# mcu_battery.net
KiCad netlist of a schematic drawn in EAGLE
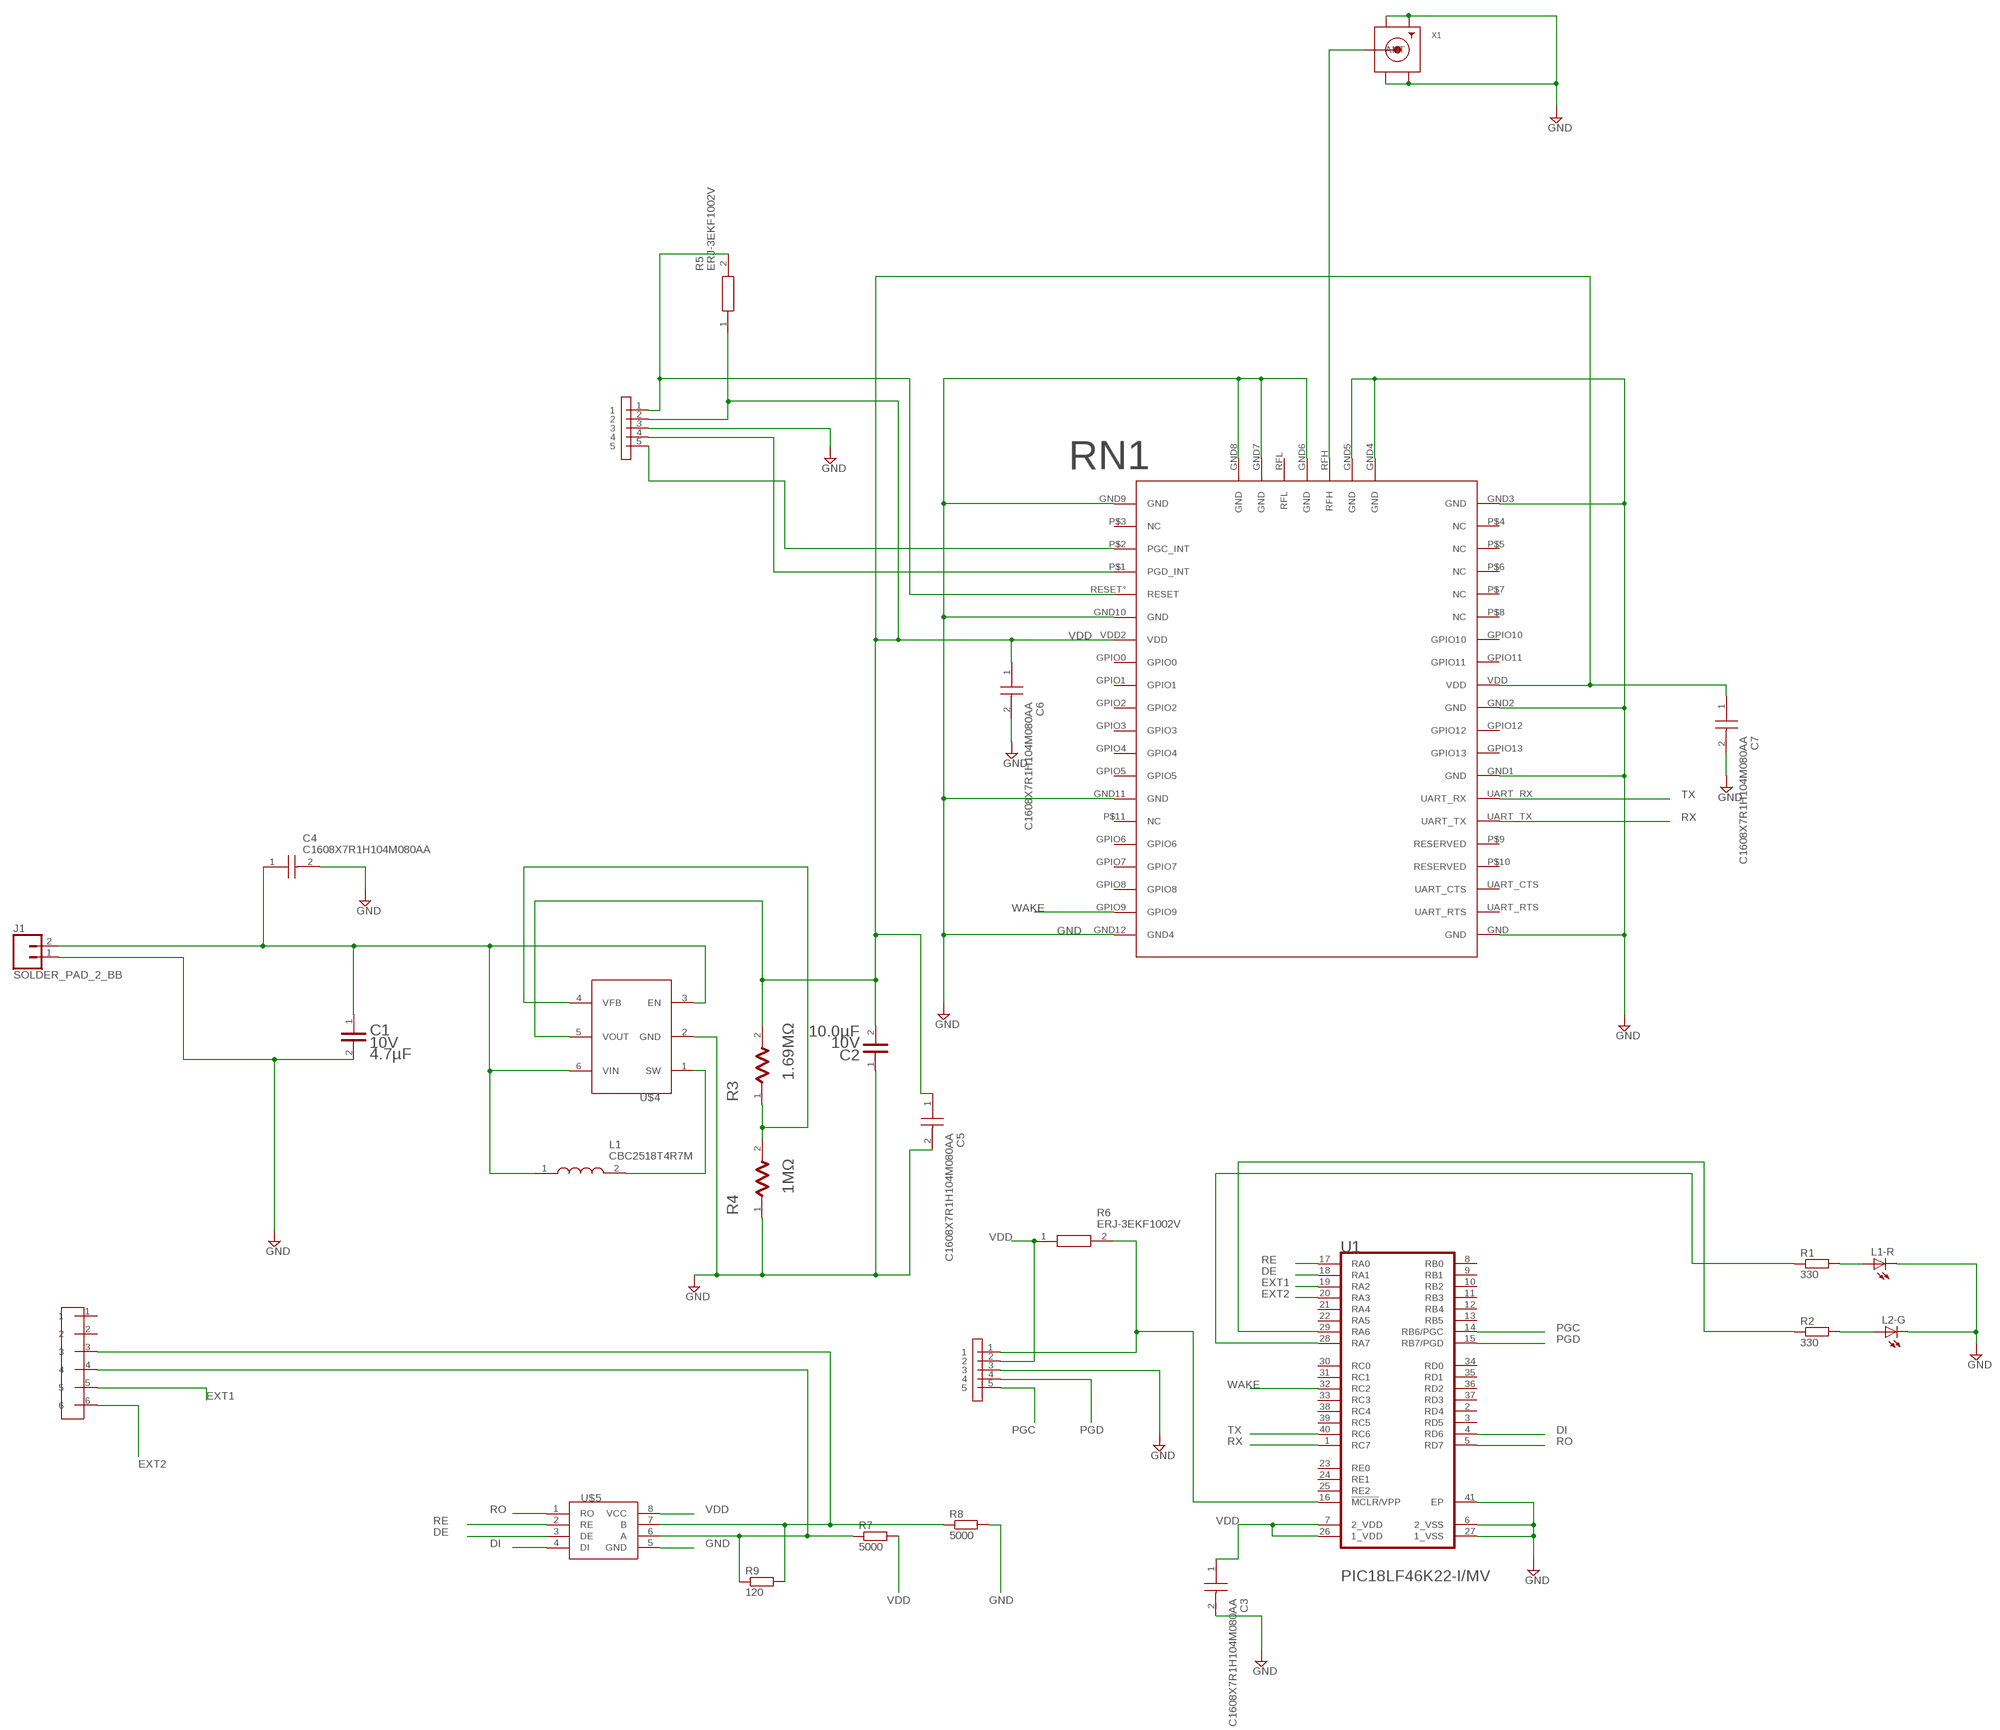
[diagram p0: schematic, sheet 1]

(export (version "E")
  (design (tool "Eeschema 10.0.6"))
  (components
    (comp (ref "C1")
      (value "KEMET_C0603C475K8PACTUKEMET_C0603C475K8PACTU_0_0")
      (footprint "eagle-import:KEMET_C0603C475K8PACTU_0")
      (fields
        (field (name "DIGIKEY_PART_NUMBER") "399-5503-1-ND")
        (field (name "MF") "Kemet")
        (field (name "MOUSER_PART_NUMBER") "80-C0603C475K8P")
      )
      (libsource (lib "eagle-import") (part "KEMET_C0603C475K8PACTUKEMET_C0603C475K8PACTU_0_0"))
    )
    (comp (ref "C2")
      (value "TDK_C1608X5R1A106M080ACTDK_C1608X5R1A106M080AC_0_0")
      (footprint "eagle-import:TDK_C1608X5R1A106M080AC_0")
      (fields
        (field (name "DIGIKEY_PART_NUMBER") "445-6853-1-ND")
        (field (name "MF") "TDK")
        (field (name "MOUSER_PART_NUMBER") "810-C1608X5R1A106M")
      )
      (libsource (lib "eagle-import") (part "TDK_C1608X5R1A106M080ACTDK_C1608X5R1A106M080AC_0_0"))
    )
    (comp (ref "C3")
      (value "C1608X7R1H104M080AA")
      (footprint "eagle-import:CAPC1608X80N")
      (fields (field (name "MOUSER_PART_NUMBER") "810-C1608X7R1H104M"))
      (libsource (lib "eagle-import") (part "C1608X7R1H104M080AA"))
    )
    (comp (ref "C4")
      (value "C1608X7R1H104M080AA")
      (footprint "eagle-import:CAPC1608X80N")
      (fields (field (name "MOUSER_PART_NUMBER") "810-C1608X7R1H104M"))
      (libsource (lib "eagle-import") (part "C1608X7R1H104M080AA"))
    )
    (comp (ref "C5")
      (value "C1608X7R1H104M080AA")
      (footprint "eagle-import:CAPC1608X80N")
      (fields (field (name "MOUSER_PART_NUMBER") "810-C1608X7R1H104M"))
      (libsource (lib "eagle-import") (part "C1608X7R1H104M080AA"))
    )
    (comp (ref "C6")
      (value "C1608X7R1H104M080AA")
      (footprint "eagle-import:CAPC1608X80N")
      (fields (field (name "MOUSER_PART_NUMBER") "810-C1608X7R1H104M"))
      (libsource (lib "eagle-import") (part "C1608X7R1H104M080AA"))
    )
    (comp (ref "C7")
      (value "C1608X7R1H104M080AA")
      (footprint "eagle-import:CAPC1608X80N")
      (fields (field (name "MOUSER_PART_NUMBER") "810-C1608X7R1H104M"))
      (libsource (lib "eagle-import") (part "C1608X7R1H104M080AA"))
    )
    (comp (ref "J1")
      (value "SOLDER_PAD_2_BB")
      (footprint "eagle-import:SOLDER_PAD_2")
      (libsource (lib "eagle-import") (part "SOLDER_PAD_2_BB"))
    )
    (comp (ref "L1")
      (value "CBC2518T4R7M")
      (footprint "eagle-import:INDC2518X200N")
      (fields (field (name "MOUSER_PART_NUMBER") "963-CBC2518T4R7M"))
      (libsource (lib "eagle-import") (part "CBC2518T4R7M"))
    )
    (comp (ref "L1-R")
      (value "LEDCHIP-LED0603")
      (footprint "eagle-import:CHIP-LED0603")
      (libsource (lib "eagle-import") (part "LEDCHIP-LED0603"))
    )
    (comp (ref "L2-G")
      (value "LEDCHIP-LED0603")
      (footprint "eagle-import:CHIP-LED0603")
      (libsource (lib "eagle-import") (part "LEDCHIP-LED0603"))
    )
    (comp (ref "R1")
      (value "330")
      (footprint "eagle-import:R0603")
      (libsource (lib "eagle-import") (part "R-EU_R0603"))
    )
    (comp (ref "R2")
      (value "330")
      (footprint "eagle-import:R0603")
      (libsource (lib "eagle-import") (part "R-EU_R0603"))
    )
    (comp (ref "R3")
      (value "VISHAY_CRCW06031M69FKEAVISHAY_CRCW06031M69FKEA_0_1")
      (footprint "eagle-import:VISHAY_CRCW06031M69FKEA_1")
      (fields
        (field (name "APPROVED_ALTERNATE_PART_NUMBER") "541-1.00HHCT-ND")
        (field (name "DIGIKEY_PART_NUMBER") "541-1.69MHTR-ND")
        (field (name "MF") "Vishay")
      )
      (libsource (lib "eagle-import") (part "VISHAY_CRCW06031M69FKEAVISHAY_CRCW06031M69FKEA_0_1"))
    )
    (comp (ref "R4")
      (value "STACKPOLE_RMCF0603FT1M00STACKPOLE_RMCF0603FT1M00_0_1")
      (footprint "eagle-import:STACKPOLE_RMCF0603FT1M00_1")
      (fields
        (field (name "APPROVED_ALTERNATE_PART_NUMBER") "541-1.00HHCT-ND")
        (field (name "DIGIKEY_PART_NUMBER") "RMCF0603FT1M00-ND")
        (field (name "MF") "Stackpole")
      )
      (libsource (lib "eagle-import") (part "STACKPOLE_RMCF0603FT1M00STACKPOLE_RMCF0603FT1M00_0_1"))
    )
    (comp (ref "R5")
      (value "ERJ-3EKF1002V")
      (footprint "eagle-import:RESC1608X55N")
      (fields (field (name "MOUSER_PART_NUMBER") "667-ERJ-3EKF1002V"))
      (libsource (lib "eagle-import") (part "ERJ-3EKF1002V"))
    )
    (comp (ref "R6")
      (value "ERJ-3EKF1002V")
      (footprint "eagle-import:RESC1608X55N")
      (fields (field (name "MOUSER_PART_NUMBER") "667-ERJ-3EKF1002V"))
      (libsource (lib "eagle-import") (part "ERJ-3EKF1002V"))
    )
    (comp (ref "R7")
      (value "5000")
      (footprint "eagle-import:R0805")
      (libsource (lib "eagle-import") (part "R-EU_R0805"))
    )
    (comp (ref "R8")
      (value "5000")
      (footprint "eagle-import:R0805")
      (libsource (lib "eagle-import") (part "R-EU_R0805"))
    )
    (comp (ref "R9")
      (value "120")
      (footprint "eagle-import:R0805")
      (libsource (lib "eagle-import") (part "R-EU_R0805"))
    )
    (comp (ref "RN1")
      (value "NEW_RN2483")
      (footprint "eagle-import:NEW_RN2483")
      (libsource (lib "eagle-import") (part "NEW_RN2483"))
    )
    (comp (ref "U$2")
      (value "ICSP52")
      (footprint "eagle-import:ICSP")
      (libsource (lib "eagle-import") (part "ICSP52"))
    )
    (comp (ref "U$3")
      (value "ICSP_V2")
      (footprint "eagle-import:ICSP_V2")
      (libsource (lib "eagle-import") (part "ICSP_V2"))
    )
    (comp (ref "U$4")
      (value "MCP16252")
      (footprint "eagle-import:MCP16252")
      (libsource (lib "eagle-import") (part "MCP16252"))
    )
    (comp (ref "U$5")
      (value "AMD3485E")
      (footprint "eagle-import:AMD3485E")
      (libsource (lib "eagle-import") (part "AMD3485E"))
    )
    (comp (ref "U1")
      (value "MICROCHIP_PIC18LF46K22-I-MVMICROCHIP_PIC18LF46K22-I-MV_0_1")
      (footprint "eagle-import:MICROCHIP_PIC18LF46K22-I-MV_1")
      (fields (field (name "MF") "Microchip") (field (name "MPN") "PIC18LF46K22-I/MV"))
      (libsource (lib "eagle-import") (part "MICROCHIP_PIC18LF46K22-I-MVMICROCHIP_PIC18LF46K22-I-MV_0_1"))
    )
    (comp (ref "U5")
      (value "CONNECTOR6_V2")
      (footprint "eagle-import:CONNECTOR6_V2")
      (libsource (lib "eagle-import") (part "CONNECTOR6_V2"))
    )
    (comp (ref "X1")
      (value "SMACONNECTOR_EDGE")
      (footprint "eagle-import:SMA_EDGELAUNCH")
      (libsource (lib "eagle-import") (part "SMACONNECTOR_EDGE"))
    )
  )
  (nets
    (net (code "1") (name "/DE") (class "Default")
      (node (ref "U$5") (pin "3") (pinfunction "DE_3") (pintype "bidirectional"))
      (node (ref "U1") (pin "18") (pinfunction "RA1_18") (pintype "bidirectional"))
    )
    (net (code "2") (name "/DI") (class "Default")
      (node (ref "U$5") (pin "4") (pinfunction "DI_4") (pintype "bidirectional"))
      (node (ref "U1") (pin "4") (pinfunction "RD6_4") (pintype "bidirectional"))
    )
    (net (code "3") (name "/EXT1") (class "Default")
      (node (ref "U1") (pin "19") (pinfunction "RA2_19") (pintype "bidirectional"))
      (node (ref "U5") (pin "5") (pinfunction "5_5") (pintype "bidirectional"))
    )
    (net (code "4") (name "/EXT2") (class "Default")
      (node (ref "U1") (pin "20") (pinfunction "RA3_20") (pintype "bidirectional"))
      (node (ref "U5") (pin "6") (pinfunction "6_6") (pintype "bidirectional"))
    )
    (net (code "5") (name "/PGC") (class "Default")
      (node (ref "U$2") (pin "5") (pinfunction "5_5") (pintype "bidirectional"))
      (node (ref "U1") (pin "14") (pinfunction "RB6/PGC_14") (pintype "bidirectional"))
    )
    (net (code "6") (name "/PGD") (class "Default")
      (node (ref "U$2") (pin "4") (pinfunction "4_4") (pintype "bidirectional"))
      (node (ref "U1") (pin "15") (pinfunction "RB7/PGD_15") (pintype "bidirectional"))
    )
    (net (code "7") (name "/RE") (class "Default")
      (node (ref "U$5") (pin "2") (pinfunction "RE_2") (pintype "bidirectional"))
      (node (ref "U1") (pin "17") (pinfunction "RA0_17") (pintype "bidirectional"))
    )
    (net (code "8") (name "/RO") (class "Default")
      (node (ref "U$5") (pin "1") (pinfunction "RO_1") (pintype "bidirectional"))
      (node (ref "U1") (pin "5") (pinfunction "RD7_5") (pintype "bidirectional"))
    )
    (net (code "9") (name "/RX") (class "Default")
      (node (ref "RN1") (pin "UART_TX") (pinfunction "UART_TX_UART_TX") (pintype "bidirectional"))
      (node (ref "U1") (pin "1") (pinfunction "RC7_1") (pintype "bidirectional"))
    )
    (net (code "10") (name "/TX") (class "Default")
      (node (ref "RN1") (pin "UART_RX") (pinfunction "UART_RX_UART_RX") (pintype "bidirectional"))
      (node (ref "U1") (pin "40") (pinfunction "RC6_40") (pintype "bidirectional"))
    )
    (net (code "11") (name "/VDD") (class "Default")
      (node (ref "C2") (pin "2") (pinfunction "2_2") (pintype "bidirectional"))
      (node (ref "C3") (pin "1") (pinfunction "1_1") (pintype "bidirectional"))
      (node (ref "C5") (pin "1") (pinfunction "1_1") (pintype "bidirectional"))
      (node (ref "C6") (pin "1") (pinfunction "1_1") (pintype "bidirectional"))
      (node (ref "C7") (pin "1") (pinfunction "1_1") (pintype "bidirectional"))
      (node (ref "R3") (pin "2") (pinfunction "2_2") (pintype "passive"))
      (node (ref "R5") (pin "1") (pinfunction "1_1") (pintype "bidirectional"))
      (node (ref "R6") (pin "1") (pinfunction "1_1") (pintype "bidirectional"))
      (node (ref "R7") (pin "2") (pinfunction "2_2") (pintype "passive"))
      (node (ref "RN1") (pin "VDD") (pinfunction "VDD_VDD") (pintype "bidirectional"))
      (node (ref "RN1") (pin "VDD2") (pinfunction "VDD_VDD2") (pintype "bidirectional"))
      (node (ref "U$2") (pin "2") (pinfunction "2_2") (pintype "bidirectional"))
      (node (ref "U$3") (pin "2") (pinfunction "2_2") (pintype "bidirectional"))
      (node (ref "U$4") (pin "5") (pinfunction "VOUT_5") (pintype "bidirectional"))
      (node (ref "U$5") (pin "8") (pinfunction "VCC_8") (pintype "bidirectional"))
      (node (ref "U1") (pin "26") (pinfunction "1_VDD_26") (pintype "power_in"))
      (node (ref "U1") (pin "7") (pinfunction "2_VDD_7") (pintype "power_in"))
    )
    (net (code "12") (name "/WAKE") (class "Default")
      (node (ref "RN1") (pin "GPIO9") (pinfunction "GPIO9_GPIO9") (pintype "bidirectional"))
      (node (ref "U1") (pin "32") (pinfunction "RC2_32") (pintype "bidirectional"))
    )
    (net (code "13") (name "GND") (class "Default")
      (node (ref "C1") (pin "2") (pinfunction "2_2") (pintype "bidirectional"))
      (node (ref "C2") (pin "1") (pinfunction "1_1") (pintype "bidirectional"))
      (node (ref "C3") (pin "2") (pinfunction "2_2") (pintype "bidirectional"))
      (node (ref "C4") (pin "2") (pinfunction "2_2") (pintype "bidirectional"))
      (node (ref "C5") (pin "2") (pinfunction "2_2") (pintype "bidirectional"))
      (node (ref "C6") (pin "2") (pinfunction "2_2") (pintype "bidirectional"))
      (node (ref "C7") (pin "2") (pinfunction "2_2") (pintype "bidirectional"))
      (node (ref "J1") (pin "1") (pinfunction "1_1") (pintype "passive"))
      (node (ref "L1-R") (pin "C") (pinfunction "C_C") (pintype "passive"))
      (node (ref "L2-G") (pin "C") (pinfunction "C_C") (pintype "passive"))
      (node (ref "R4") (pin "1") (pinfunction "1_1") (pintype "passive"))
      (node (ref "R8") (pin "2") (pinfunction "2_2") (pintype "passive"))
      (node (ref "RN1") (pin "GND") (pinfunction "GND_GND") (pintype "bidirectional"))
      (node (ref "RN1") (pin "GND1") (pinfunction "GND_GND1") (pintype "bidirectional"))
      (node (ref "RN1") (pin "GND10") (pinfunction "GND_GND10") (pintype "bidirectional"))
      (node (ref "RN1") (pin "GND11") (pinfunction "GND_GND11") (pintype "bidirectional"))
      (node (ref "RN1") (pin "GND12") (pinfunction "GND4_GND12") (pintype "bidirectional"))
      (node (ref "RN1") (pin "GND2") (pinfunction "GND_GND2") (pintype "bidirectional"))
      (node (ref "RN1") (pin "GND3") (pinfunction "GND_GND3") (pintype "bidirectional"))
      (node (ref "RN1") (pin "GND4") (pinfunction "GND_GND4") (pintype "bidirectional"))
      (node (ref "RN1") (pin "GND5") (pinfunction "GND_GND5") (pintype "bidirectional"))
      (node (ref "RN1") (pin "GND6") (pinfunction "GND_GND6") (pintype "bidirectional"))
      (node (ref "RN1") (pin "GND7") (pinfunction "GND_GND7") (pintype "bidirectional"))
      (node (ref "RN1") (pin "GND8") (pinfunction "GND_GND8") (pintype "bidirectional"))
      (node (ref "RN1") (pin "GND9") (pinfunction "GND_GND9") (pintype "bidirectional"))
      (node (ref "U$2") (pin "3") (pinfunction "3_3") (pintype "bidirectional"))
      (node (ref "U$3") (pin "3") (pinfunction "3_3") (pintype "bidirectional"))
      (node (ref "U$4") (pin "2") (pinfunction "GND_2") (pintype "bidirectional"))
      (node (ref "U$5") (pin "5") (pinfunction "GND_5") (pintype "bidirectional"))
      (node (ref "U1") (pin "27") (pinfunction "1_VSS_27") (pintype "power_in"))
      (node (ref "U1") (pin "41") (pinfunction "EP_41") (pintype "passive"))
      (node (ref "U1") (pin "6") (pinfunction "2_VSS_6") (pintype "power_in"))
      (node (ref "X1") (pin "GND@1") (pinfunction "GND4_GND@1") (pintype "power_in"))
      (node (ref "X1") (pin "GND@2") (pinfunction "GND3_GND@2") (pintype "power_in"))
      (node (ref "X1") (pin "GND@3") (pinfunction "GND2_GND@3") (pintype "power_in"))
      (node (ref "X1") (pin "GND@4") (pinfunction "GND1_GND@4") (pintype "power_in"))
    )
    (net (code "14") (name "Net-(L1-R-PadA)") (class "Default")
      (node (ref "L1-R") (pin "A") (pinfunction "A_A") (pintype "passive"))
      (node (ref "R1") (pin "2") (pinfunction "2_2") (pintype "passive"))
    )
    (net (code "15") (name "Net-(L2-G-PadA)") (class "Default")
      (node (ref "L2-G") (pin "A") (pinfunction "A_A") (pintype "passive"))
      (node (ref "R2") (pin "2") (pinfunction "2_2") (pintype "passive"))
    )
    (net (code "16") (name "Net-(RN1-PGC_INT)") (class "Default")
      (node (ref "RN1") (pin "P$2") (pinfunction "PGC_INT_P$2") (pintype "bidirectional"))
      (node (ref "U$3") (pin "5") (pinfunction "5_5") (pintype "bidirectional"))
    )
    (net (code "17") (name "Net-(RN1-PGD_INT)") (class "Default")
      (node (ref "RN1") (pin "P$1") (pinfunction "PGD_INT_P$1") (pintype "bidirectional"))
      (node (ref "U$3") (pin "4") (pinfunction "4_4") (pintype "bidirectional"))
    )
    (net (code "18") (name "Net-(RN1-RESET)") (class "Default")
      (node (ref "R5") (pin "2") (pinfunction "2_2") (pintype "bidirectional"))
      (node (ref "RN1") (pin "RESET°") (pinfunction "RESET_RESET°") (pintype "bidirectional"))
      (node (ref "U$3") (pin "1") (pinfunction "1_1") (pintype "bidirectional"))
    )
    (net (code "19") (name "Net-(U$4-EN)") (class "Default")
      (node (ref "C1") (pin "1") (pinfunction "1_1") (pintype "bidirectional"))
      (node (ref "C4") (pin "1") (pinfunction "1_1") (pintype "bidirectional"))
      (node (ref "J1") (pin "2") (pinfunction "2_2") (pintype "passive"))
      (node (ref "L1") (pin "1") (pinfunction "1_1") (pintype "bidirectional"))
      (node (ref "U$4") (pin "3") (pinfunction "EN_3") (pintype "bidirectional"))
      (node (ref "U$4") (pin "6") (pinfunction "VIN_6") (pintype "bidirectional"))
    )
    (net (code "20") (name "Net-(U$4-SW)") (class "Default")
      (node (ref "L1") (pin "2") (pinfunction "2_2") (pintype "bidirectional"))
      (node (ref "U$4") (pin "1") (pinfunction "SW_1") (pintype "bidirectional"))
    )
    (net (code "21") (name "Net-(U$4-VFB)") (class "Default")
      (node (ref "R3") (pin "1") (pinfunction "1_1") (pintype "passive"))
      (node (ref "R4") (pin "2") (pinfunction "2_2") (pintype "passive"))
      (node (ref "U$4") (pin "4") (pinfunction "VFB_4") (pintype "bidirectional"))
    )
    (net (code "22") (name "Net-(U$5-A)") (class "Default")
      (node (ref "R7") (pin "1") (pinfunction "1_1") (pintype "passive"))
      (node (ref "R9") (pin "1") (pinfunction "1_1") (pintype "passive"))
      (node (ref "U$5") (pin "6") (pinfunction "A_6") (pintype "bidirectional"))
      (node (ref "U5") (pin "4") (pinfunction "4_4") (pintype "bidirectional"))
    )
    (net (code "23") (name "Net-(U$5-B)") (class "Default")
      (node (ref "R8") (pin "1") (pinfunction "1_1") (pintype "passive"))
      (node (ref "R9") (pin "2") (pinfunction "2_2") (pintype "passive"))
      (node (ref "U$5") (pin "7") (pinfunction "B_7") (pintype "bidirectional"))
      (node (ref "U5") (pin "3") (pinfunction "3_3") (pintype "bidirectional"))
    )
    (net (code "24") (name "Net-(U1-RA6)") (class "Default")
      (node (ref "R2") (pin "1") (pinfunction "1_1") (pintype "passive"))
      (node (ref "U1") (pin "29") (pinfunction "RA6_29") (pintype "bidirectional"))
    )
    (net (code "25") (name "Net-(U1-RA7)") (class "Default")
      (node (ref "R1") (pin "1") (pinfunction "1_1") (pintype "passive"))
      (node (ref "U1") (pin "28") (pinfunction "RA7_28") (pintype "bidirectional"))
    )
    (net (code "26") (name "Net-(U1-~{MCLR}{slash}VPP)") (class "Default")
      (node (ref "R6") (pin "2") (pinfunction "2_2") (pintype "bidirectional"))
      (node (ref "U$2") (pin "1") (pinfunction "1_1") (pintype "bidirectional"))
      (node (ref "U1") (pin "16") (pinfunction "~{MCLR}/VPP_16") (pintype "input"))
    )
    (net (code "27") (name "Net-(X1-ANT)") (class "Default")
      (node (ref "RN1") (pin "RFH") (pinfunction "RFH_RFH") (pintype "bidirectional"))
      (node (ref "X1") (pin "P") (pinfunction "ANT_P") (pintype "bidirectional"))
    )
    (net (code "28") (name "unconnected-(RN1-NC-PadP$3)") (class "Default")
      (node (ref "RN1") (pin "P$3") (pinfunction "NC_P$3") (pintype "bidirectional"))
    )
    (net (code "29") (name "unconnected-(RN1-NC-PadP$4)") (class "Default")
      (node (ref "RN1") (pin "P$4") (pinfunction "NC_P$4") (pintype "bidirectional"))
    )
    (net (code "30") (name "unconnected-(RN1-NC-PadP$5)") (class "Default")
      (node (ref "RN1") (pin "P$5") (pinfunction "NC_P$5") (pintype "bidirectional"))
    )
    (net (code "31") (name "unconnected-(RN1-NC-PadP$6)") (class "Default")
      (node (ref "RN1") (pin "P$6") (pinfunction "NC_P$6") (pintype "bidirectional"))
    )
    (net (code "32") (name "unconnected-(RN1-NC-PadP$7)") (class "Default")
      (node (ref "RN1") (pin "P$7") (pinfunction "NC_P$7") (pintype "bidirectional"))
    )
    (net (code "33") (name "unconnected-(RN1-NC-PadP$8)") (class "Default")
      (node (ref "RN1") (pin "P$8") (pinfunction "NC_P$8") (pintype "bidirectional"))
    )
    (net (code "34") (name "unconnected-(RN1-NC-PadP$11)") (class "Default")
      (node (ref "RN1") (pin "P$11") (pinfunction "NC_P$11") (pintype "bidirectional"))
    )
    (net (code "35") (name "unconnected-(RN1-PadGPIO0)") (class "Default")
      (node (ref "RN1") (pin "GPIO0") (pinfunction "GPIO0_GPIO0") (pintype "bidirectional"))
    )
    (net (code "36") (name "unconnected-(RN1-PadGPIO1)") (class "Default")
      (node (ref "RN1") (pin "GPIO1") (pinfunction "GPIO1_GPIO1") (pintype "bidirectional"))
    )
    (net (code "37") (name "unconnected-(RN1-PadGPIO2)") (class "Default")
      (node (ref "RN1") (pin "GPIO2") (pinfunction "GPIO2_GPIO2") (pintype "bidirectional"))
    )
    (net (code "38") (name "unconnected-(RN1-PadGPIO3)") (class "Default")
      (node (ref "RN1") (pin "GPIO3") (pinfunction "GPIO3_GPIO3") (pintype "bidirectional"))
    )
    (net (code "39") (name "unconnected-(RN1-PadGPIO4)") (class "Default")
      (node (ref "RN1") (pin "GPIO4") (pinfunction "GPIO4_GPIO4") (pintype "bidirectional"))
    )
    (net (code "40") (name "unconnected-(RN1-PadGPIO5)") (class "Default")
      (node (ref "RN1") (pin "GPIO5") (pinfunction "GPIO5_GPIO5") (pintype "bidirectional"))
    )
    (net (code "41") (name "unconnected-(RN1-PadGPIO6)") (class "Default")
      (node (ref "RN1") (pin "GPIO6") (pinfunction "GPIO6_GPIO6") (pintype "bidirectional"))
    )
    (net (code "42") (name "unconnected-(RN1-PadGPIO7)") (class "Default")
      (node (ref "RN1") (pin "GPIO7") (pinfunction "GPIO7_GPIO7") (pintype "bidirectional"))
    )
    (net (code "43") (name "unconnected-(RN1-PadGPIO8)") (class "Default")
      (node (ref "RN1") (pin "GPIO8") (pinfunction "GPIO8_GPIO8") (pintype "bidirectional"))
    )
    (net (code "44") (name "unconnected-(RN1-PadGPIO10)") (class "Default")
      (node (ref "RN1") (pin "GPIO10") (pinfunction "GPIO10_GPIO10") (pintype "bidirectional"))
    )
    (net (code "45") (name "unconnected-(RN1-PadGPIO11)") (class "Default")
      (node (ref "RN1") (pin "GPIO11") (pinfunction "GPIO11_GPIO11") (pintype "bidirectional"))
    )
    (net (code "46") (name "unconnected-(RN1-PadGPIO12)") (class "Default")
      (node (ref "RN1") (pin "GPIO12") (pinfunction "GPIO12_GPIO12") (pintype "bidirectional"))
    )
    (net (code "47") (name "unconnected-(RN1-PadGPIO13)") (class "Default")
      (node (ref "RN1") (pin "GPIO13") (pinfunction "GPIO13_GPIO13") (pintype "bidirectional"))
    )
    (net (code "48") (name "unconnected-(RN1-PadRFL)") (class "Default")
      (node (ref "RN1") (pin "RFL") (pinfunction "RFL_RFL") (pintype "bidirectional"))
    )
    (net (code "49") (name "unconnected-(RN1-PadUART_CTS)") (class "Default")
      (node (ref "RN1") (pin "UART_CTS") (pinfunction "UART_CTS_UART_CTS") (pintype "bidirectional"))
    )
    (net (code "50") (name "unconnected-(RN1-PadUART_RTS)") (class "Default")
      (node (ref "RN1") (pin "UART_RTS") (pinfunction "UART_RTS_UART_RTS") (pintype "bidirectional"))
    )
    (net (code "51") (name "unconnected-(RN1-RESERVED-PadP$9)") (class "Default")
      (node (ref "RN1") (pin "P$9") (pinfunction "RESERVED_P$9") (pintype "bidirectional"))
    )
    (net (code "52") (name "unconnected-(RN1-RESERVED-PadP$10)") (class "Default")
      (node (ref "RN1") (pin "P$10") (pinfunction "RESERVED_P$10") (pintype "bidirectional"))
    )
    (net (code "53") (name "unconnected-(U1-RA4-Pad21)") (class "Default")
      (node (ref "U1") (pin "21") (pinfunction "RA4_21") (pintype "bidirectional"))
    )
    (net (code "54") (name "unconnected-(U1-RA5-Pad22)") (class "Default")
      (node (ref "U1") (pin "22") (pinfunction "RA5_22") (pintype "bidirectional"))
    )
    (net (code "55") (name "unconnected-(U1-RB0-Pad8)") (class "Default")
      (node (ref "U1") (pin "8") (pinfunction "RB0_8") (pintype "bidirectional"))
    )
    (net (code "56") (name "unconnected-(U1-RB1-Pad9)") (class "Default")
      (node (ref "U1") (pin "9") (pinfunction "RB1_9") (pintype "bidirectional"))
    )
    (net (code "57") (name "unconnected-(U1-RB2-Pad10)") (class "Default")
      (node (ref "U1") (pin "10") (pinfunction "RB2_10") (pintype "bidirectional"))
    )
    (net (code "58") (name "unconnected-(U1-RB3-Pad11)") (class "Default")
      (node (ref "U1") (pin "11") (pinfunction "RB3_11") (pintype "bidirectional"))
    )
    (net (code "59") (name "unconnected-(U1-RB4-Pad12)") (class "Default")
      (node (ref "U1") (pin "12") (pinfunction "RB4_12") (pintype "bidirectional"))
    )
    (net (code "60") (name "unconnected-(U1-RB5-Pad13)") (class "Default")
      (node (ref "U1") (pin "13") (pinfunction "RB5_13") (pintype "bidirectional"))
    )
    (net (code "61") (name "unconnected-(U1-RC0-Pad30)") (class "Default")
      (node (ref "U1") (pin "30") (pinfunction "RC0_30") (pintype "bidirectional"))
    )
    (net (code "62") (name "unconnected-(U1-RC1-Pad31)") (class "Default")
      (node (ref "U1") (pin "31") (pinfunction "RC1_31") (pintype "bidirectional"))
    )
    (net (code "63") (name "unconnected-(U1-RC3-Pad33)") (class "Default")
      (node (ref "U1") (pin "33") (pinfunction "RC3_33") (pintype "bidirectional"))
    )
    (net (code "64") (name "unconnected-(U1-RC4-Pad38)") (class "Default")
      (node (ref "U1") (pin "38") (pinfunction "RC4_38") (pintype "bidirectional"))
    )
    (net (code "65") (name "unconnected-(U1-RC5-Pad39)") (class "Default")
      (node (ref "U1") (pin "39") (pinfunction "RC5_39") (pintype "bidirectional"))
    )
    (net (code "66") (name "unconnected-(U1-RD0-Pad34)") (class "Default")
      (node (ref "U1") (pin "34") (pinfunction "RD0_34") (pintype "bidirectional"))
    )
    (net (code "67") (name "unconnected-(U1-RD1-Pad35)") (class "Default")
      (node (ref "U1") (pin "35") (pinfunction "RD1_35") (pintype "bidirectional"))
    )
    (net (code "68") (name "unconnected-(U1-RD2-Pad36)") (class "Default")
      (node (ref "U1") (pin "36") (pinfunction "RD2_36") (pintype "bidirectional"))
    )
    (net (code "69") (name "unconnected-(U1-RD3-Pad37)") (class "Default")
      (node (ref "U1") (pin "37") (pinfunction "RD3_37") (pintype "bidirectional"))
    )
    (net (code "70") (name "unconnected-(U1-RD4-Pad2)") (class "Default")
      (node (ref "U1") (pin "2") (pinfunction "RD4_2") (pintype "bidirectional"))
    )
    (net (code "71") (name "unconnected-(U1-RD5-Pad3)") (class "Default")
      (node (ref "U1") (pin "3") (pinfunction "RD5_3") (pintype "bidirectional"))
    )
    (net (code "72") (name "unconnected-(U1-RE0-Pad23)") (class "Default")
      (node (ref "U1") (pin "23") (pinfunction "RE0_23") (pintype "bidirectional"))
    )
    (net (code "73") (name "unconnected-(U1-RE1-Pad24)") (class "Default")
      (node (ref "U1") (pin "24") (pinfunction "RE1_24") (pintype "bidirectional"))
    )
    (net (code "74") (name "unconnected-(U1-RE2-Pad25)") (class "Default")
      (node (ref "U1") (pin "25") (pinfunction "RE2_25") (pintype "bidirectional"))
    )
    (net (code "75") (name "unconnected-(U5-Pad1)") (class "Default")
      (node (ref "U5") (pin "1") (pinfunction "1_1") (pintype "bidirectional"))
    )
    (net (code "76") (name "unconnected-(U5-Pad2)") (class "Default")
      (node (ref "U5") (pin "2") (pinfunction "2_2") (pintype "bidirectional"))
    )
  )
)
